# v1.net
KiCad netlist of a schematic drawn in EAGLE
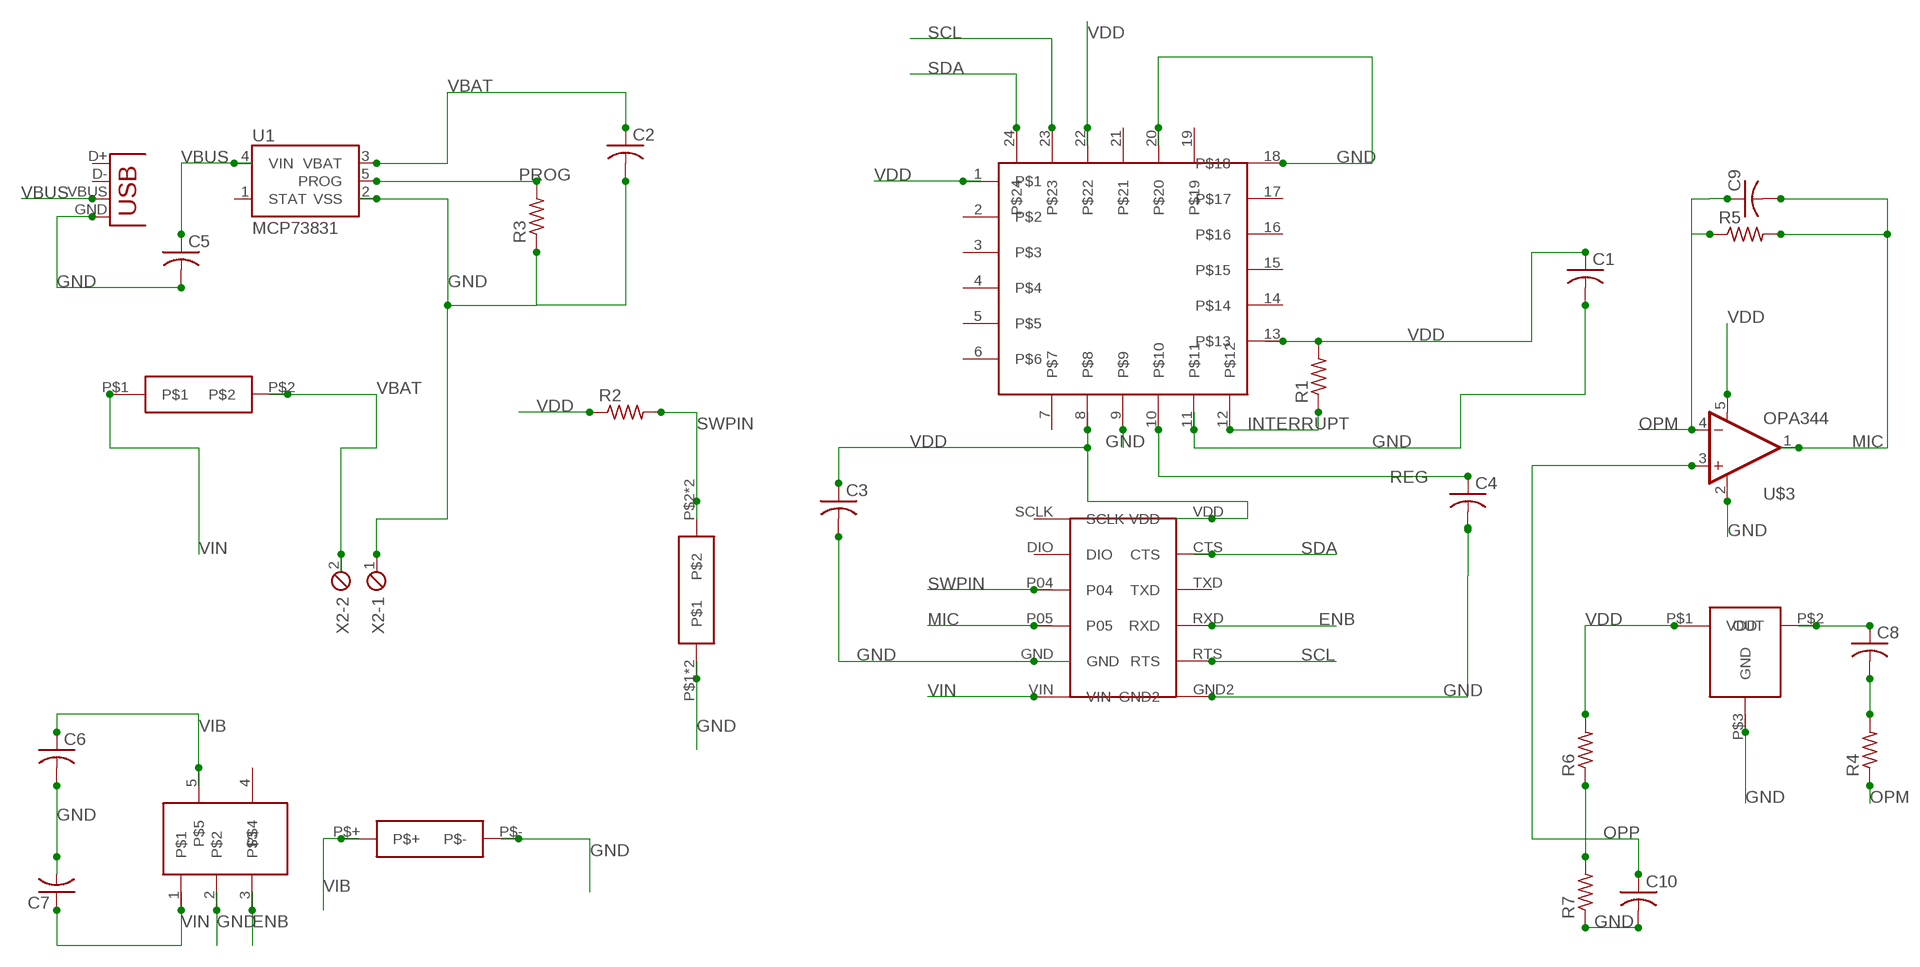
[diagram p0: schematic, sheet 1]

(export (version "E")
  (design (tool "Eeschema 10.0.6"))
  (components
    (comp (ref "C1")
      (value "C-USC0402K")
      (footprint "eagle-import:C0402K")
      (libsource (lib "eagle-import") (part "C-USC0402K"))
    )
    (comp (ref "C2")
      (value "C-USC0402K")
      (footprint "eagle-import:C0402K")
      (libsource (lib "eagle-import") (part "C-USC0402K"))
    )
    (comp (ref "C3")
      (value "C-USC0402K")
      (footprint "eagle-import:C0402K")
      (libsource (lib "eagle-import") (part "C-USC0402K"))
    )
    (comp (ref "C4")
      (value "C-USC0402K")
      (footprint "eagle-import:C0402K")
      (libsource (lib "eagle-import") (part "C-USC0402K"))
    )
    (comp (ref "C5")
      (value "C-USC0402K")
      (footprint "eagle-import:C0402K")
      (libsource (lib "eagle-import") (part "C-USC0402K"))
    )
    (comp (ref "C6")
      (value "C-USC0402K")
      (footprint "eagle-import:C0402K")
      (libsource (lib "eagle-import") (part "C-USC0402K"))
    )
    (comp (ref "C7")
      (value "C-USC0402K")
      (footprint "eagle-import:C0402K")
      (libsource (lib "eagle-import") (part "C-USC0402K"))
    )
    (comp (ref "C8")
      (value "C-USC0402K")
      (footprint "eagle-import:C0402K")
      (libsource (lib "eagle-import") (part "C-USC0402K"))
    )
    (comp (ref "C9")
      (value "C-USC0402K")
      (footprint "eagle-import:C0402K")
      (libsource (lib "eagle-import") (part "C-USC0402K"))
    )
    (comp (ref "C10")
      (value "C-USC0402K")
      (footprint "eagle-import:C0402K")
      (libsource (lib "eagle-import") (part "C-USC0402K"))
    )
    (comp (ref "R1")
      (value "R-US_R0402")
      (footprint "eagle-import:R0402")
      (libsource (lib "eagle-import") (part "R-US_R0402"))
    )
    (comp (ref "R2")
      (value "R-US_R0402")
      (footprint "eagle-import:R0402")
      (libsource (lib "eagle-import") (part "R-US_R0402"))
    )
    (comp (ref "R3")
      (value "R-US_R0402")
      (footprint "eagle-import:R0402")
      (libsource (lib "eagle-import") (part "R-US_R0402"))
    )
    (comp (ref "R4")
      (value "R-US_R0402")
      (footprint "eagle-import:R0402")
      (libsource (lib "eagle-import") (part "R-US_R0402"))
    )
    (comp (ref "R5")
      (value "R-US_R0402")
      (footprint "eagle-import:R0402")
      (libsource (lib "eagle-import") (part "R-US_R0402"))
    )
    (comp (ref "R6")
      (value "R-US_R0402")
      (footprint "eagle-import:R0402")
      (libsource (lib "eagle-import") (part "R-US_R0402"))
    )
    (comp (ref "R7")
      (value "R-US_R0402")
      (footprint "eagle-import:R0402")
      (libsource (lib "eagle-import") (part "R-US_R0402"))
    )
    (comp (ref "U$1")
      (value "NANOBLE")
      (footprint "eagle-import:NANOBLE")
      (libsource (lib "eagle-import") (part "NANOBLE"))
    )
    (comp (ref "U$2")
      (value "MICROPHONE")
      (footprint "eagle-import:MICROPHONE")
      (libsource (lib "eagle-import") (part "MICROPHONE"))
    )
    (comp (ref "U$3")
      (value "OPA344")
      (footprint "eagle-import:SOT23-5")
      (libsource (lib "eagle-import") (part "OPA344"))
    )
    (comp (ref "U$4")
      (value "LP5907")
      (footprint "eagle-import:SOT23-5")
      (libsource (lib "eagle-import") (part "LP5907"))
    )
    (comp (ref "U$5")
      (value "TACTILE")
      (footprint "eagle-import:TACTILE")
      (libsource (lib "eagle-import") (part "TACTILE"))
    )
    (comp (ref "U$6")
      (value "SWITCH")
      (footprint "eagle-import:SWITCH2")
      (libsource (lib "eagle-import") (part "SWITCH"))
    )
    (comp (ref "U$7")
      (value "VIBRATOR")
      (footprint "eagle-import:VIBRATOR")
      (libsource (lib "eagle-import") (part "VIBRATOR"))
    )
    (comp (ref "U$8")
      (value "COMPASSE")
      (footprint "eagle-import:QFN-24-USB")
      (libsource (lib "eagle-import") (part "COMPASSE"))
    )
    (comp (ref "U1")
      (value "MCP73831")
      (footprint "eagle-import:SOT23-5")
      (libsource (lib "eagle-import") (part "MCP73831"))
    )
    (comp (ref "X1")
      (value "USB-MICROB")
      (footprint "eagle-import:USB-MICROB")
      (libsource (lib "eagle-import") (part "USB-MICROB"))
    )
    (comp (ref "X2")
      (value "MPT2")
      (footprint "eagle-import:2POL254")
      (libsource (lib "eagle-import") (part "MPT2"))
    )
  )
  (nets
    (net (code "1") (name "/ENB") (class "Default")
      (node (ref "U$1") (pin "RXD") (pinfunction "RXD_RXD") (pintype "bidirectional"))
      (node (ref "U$4") (pin "3") (pinfunction "P$3_3") (pintype "bidirectional"))
    )
    (net (code "2") (name "/GND") (class "Default")
      (node (ref "C1") (pin "2") (pinfunction "2_2") (pintype "passive"))
      (node (ref "C10") (pin "2") (pinfunction "2_2") (pintype "passive"))
      (node (ref "C2") (pin "2") (pinfunction "2_2") (pintype "passive"))
      (node (ref "C3") (pin "2") (pinfunction "2_2") (pintype "passive"))
      (node (ref "C4") (pin "2") (pinfunction "2_2") (pintype "passive"))
      (node (ref "C5") (pin "2") (pinfunction "2_2") (pintype "passive"))
      (node (ref "C6") (pin "2") (pinfunction "2_2") (pintype "passive"))
      (node (ref "C7") (pin "2") (pinfunction "2_2") (pintype "passive"))
      (node (ref "R3") (pin "1") (pinfunction "1_1") (pintype "passive"))
      (node (ref "R7") (pin "1") (pinfunction "1_1") (pintype "passive"))
      (node (ref "U$1") (pin "GND") (pinfunction "GND_GND") (pintype "bidirectional"))
      (node (ref "U$1") (pin "GND2") (pinfunction "GND2_GND2") (pintype "bidirectional"))
      (node (ref "U$2") (pin "P$3") (pinfunction "GND_P$3") (pintype "bidirectional"))
      (node (ref "U$3") (pin "2") (pinfunction "V-_2") (pintype "power_in"))
      (node (ref "U$4") (pin "2") (pinfunction "P$2_2") (pintype "bidirectional"))
      (node (ref "U$5") (pin "P$1") (pinfunction "P$1_P$1") (pintype "bidirectional"))
      (node (ref "U$5") (pin "P$3") (pinfunction "P$1_P$3") (pintype "bidirectional"))
      (node (ref "U$7") (pin "P$-") (pinfunction "P$-_P$-") (pintype "bidirectional"))
      (node (ref "U$8") (pin "11") (pinfunction "P$11_11") (pintype "bidirectional"))
      (node (ref "U$8") (pin "18") (pinfunction "P$18_18") (pintype "bidirectional"))
      (node (ref "U$8") (pin "20") (pinfunction "P$20_20") (pintype "bidirectional"))
      (node (ref "U$8") (pin "9") (pinfunction "P$9_9") (pintype "bidirectional"))
      (node (ref "U1") (pin "2") (pinfunction "VSS_2") (pintype "power_in"))
      (node (ref "X1") (pin "GND") (pinfunction "GND_GND") (pintype "bidirectional"))
      (node (ref "X2") (pin "1") (pinfunction "1_1") (pintype "passive"))
    )
    (net (code "3") (name "/INTERRUPT") (class "Default")
      (node (ref "R1") (pin "1") (pinfunction "1_1") (pintype "passive"))
      (node (ref "U$8") (pin "12") (pinfunction "P$12_12") (pintype "bidirectional"))
    )
    (net (code "4") (name "/MIC") (class "Default")
      (node (ref "C9") (pin "2") (pinfunction "2_2") (pintype "passive"))
      (node (ref "R5") (pin "2") (pinfunction "2_2") (pintype "passive"))
      (node (ref "U$1") (pin "P05") (pinfunction "P05_P05") (pintype "bidirectional"))
      (node (ref "U$3") (pin "1") (pinfunction "OUT_1") (pintype "output"))
    )
    (net (code "5") (name "/OPM") (class "Default")
      (node (ref "C9") (pin "1") (pinfunction "1_1") (pintype "passive"))
      (node (ref "R4") (pin "1") (pinfunction "1_1") (pintype "passive"))
      (node (ref "R5") (pin "1") (pinfunction "1_1") (pintype "passive"))
      (node (ref "U$3") (pin "4") (pinfunction "-IN_4") (pintype "input"))
    )
    (net (code "6") (name "/OPP") (class "Default")
      (node (ref "C10") (pin "1") (pinfunction "1_1") (pintype "passive"))
      (node (ref "R6") (pin "1") (pinfunction "1_1") (pintype "passive"))
      (node (ref "R7") (pin "2") (pinfunction "2_2") (pintype "passive"))
      (node (ref "U$3") (pin "3") (pinfunction "+IN_3") (pintype "input"))
    )
    (net (code "7") (name "/PROG") (class "Default")
      (node (ref "R3") (pin "2") (pinfunction "2_2") (pintype "passive"))
      (node (ref "U1") (pin "5") (pinfunction "PROG_5") (pintype "input"))
    )
    (net (code "8") (name "/REG") (class "Default")
      (node (ref "C4") (pin "1") (pinfunction "1_1") (pintype "passive"))
      (node (ref "U$8") (pin "10") (pinfunction "P$10_10") (pintype "bidirectional"))
    )
    (net (code "9") (name "/SCL") (class "Default")
      (node (ref "U$1") (pin "RTS") (pinfunction "RTS_RTS") (pintype "bidirectional"))
      (node (ref "U$8") (pin "23") (pinfunction "P$23_23") (pintype "bidirectional"))
    )
    (net (code "10") (name "/SDA") (class "Default")
      (node (ref "U$1") (pin "CTS") (pinfunction "CTS_CTS") (pintype "bidirectional"))
      (node (ref "U$8") (pin "24") (pinfunction "P$24_24") (pintype "bidirectional"))
    )
    (net (code "11") (name "/SWPIN") (class "Default")
      (node (ref "R2") (pin "2") (pinfunction "2_2") (pintype "passive"))
      (node (ref "U$1") (pin "P04") (pinfunction "P04_P04") (pintype "bidirectional"))
      (node (ref "U$5") (pin "P$2") (pinfunction "P$2_P$2") (pintype "bidirectional"))
      (node (ref "U$5") (pin "P$4") (pinfunction "P$2_P$4") (pintype "bidirectional"))
    )
    (net (code "12") (name "/VBAT") (class "Default")
      (node (ref "C2") (pin "1") (pinfunction "1_1") (pintype "passive"))
      (node (ref "U$6") (pin "P$2") (pinfunction "P$2_P$2") (pintype "bidirectional"))
      (node (ref "U1") (pin "3") (pinfunction "VBAT_3") (pintype "power_in"))
      (node (ref "X2") (pin "2") (pinfunction "1_2") (pintype "passive"))
    )
    (net (code "13") (name "/VBUS") (class "Default")
      (node (ref "C5") (pin "1") (pinfunction "1_1") (pintype "passive"))
      (node (ref "U1") (pin "4") (pinfunction "VIN_4") (pintype "power_in"))
      (node (ref "X1") (pin "VBUS") (pinfunction "VBUS_VBUS") (pintype "bidirectional"))
    )
    (net (code "14") (name "/VDD") (class "Default")
      (node (ref "C1") (pin "1") (pinfunction "1_1") (pintype "passive"))
      (node (ref "C3") (pin "1") (pinfunction "1_1") (pintype "passive"))
      (node (ref "R1") (pin "2") (pinfunction "2_2") (pintype "passive"))
      (node (ref "R2") (pin "1") (pinfunction "1_1") (pintype "passive"))
      (node (ref "R6") (pin "2") (pinfunction "2_2") (pintype "passive"))
      (node (ref "U$1") (pin "VDD") (pinfunction "VDD_VDD") (pintype "bidirectional"))
      (node (ref "U$2") (pin "P$1") (pinfunction "VDD_P$1") (pintype "bidirectional"))
      (node (ref "U$3") (pin "5") (pinfunction "V+_5") (pintype "power_in"))
      (node (ref "U$8") (pin "1") (pinfunction "P$1_1") (pintype "bidirectional"))
      (node (ref "U$8") (pin "13") (pinfunction "P$13_13") (pintype "bidirectional"))
      (node (ref "U$8") (pin "22") (pinfunction "P$22_22") (pintype "bidirectional"))
      (node (ref "U$8") (pin "8") (pinfunction "P$8_8") (pintype "bidirectional"))
    )
    (net (code "15") (name "/VIB") (class "Default")
      (node (ref "C6") (pin "1") (pinfunction "1_1") (pintype "passive"))
      (node (ref "U$4") (pin "5") (pinfunction "P$5_5") (pintype "bidirectional"))
      (node (ref "U$7") (pin "P$+") (pinfunction "P$+_P$+") (pintype "bidirectional"))
    )
    (net (code "16") (name "/VIN") (class "Default")
      (node (ref "C7") (pin "1") (pinfunction "1_1") (pintype "passive"))
      (node (ref "U$1") (pin "VIN") (pinfunction "VIN_VIN") (pintype "bidirectional"))
      (node (ref "U$4") (pin "1") (pinfunction "P$1_1") (pintype "bidirectional"))
      (node (ref "U$6") (pin "P$1") (pinfunction "P$1_P$1") (pintype "bidirectional"))
    )
    (net (code "17") (name "Net-(C8-Pad2)") (class "Default")
      (node (ref "C8") (pin "2") (pinfunction "2_2") (pintype "passive"))
      (node (ref "R4") (pin "2") (pinfunction "2_2") (pintype "passive"))
    )
    (net (code "18") (name "Net-(U$2-OUT)") (class "Default")
      (node (ref "C8") (pin "1") (pinfunction "1_1") (pintype "passive"))
      (node (ref "U$2") (pin "P$2") (pinfunction "OUT_P$2") (pintype "bidirectional"))
    )
    (net (code "19") (name "unconnected-(U$1-PadDIO)") (class "Default")
      (node (ref "U$1") (pin "DIO") (pinfunction "DIO_DIO") (pintype "bidirectional"))
    )
    (net (code "20") (name "unconnected-(U$1-PadSCLK)") (class "Default")
      (node (ref "U$1") (pin "SCLK") (pinfunction "SCLK_SCLK") (pintype "bidirectional"))
    )
    (net (code "21") (name "unconnected-(U$1-PadTXD)") (class "Default")
      (node (ref "U$1") (pin "TXD") (pinfunction "TXD_TXD") (pintype "bidirectional"))
    )
    (net (code "22") (name "unconnected-(U$4-P$4-Pad4)") (class "Default")
      (node (ref "U$4") (pin "4") (pinfunction "P$4_4") (pintype "bidirectional"))
    )
    (net (code "23") (name "unconnected-(U$8-P$2-Pad2)") (class "Default")
      (node (ref "U$8") (pin "2") (pinfunction "P$2_2") (pintype "bidirectional"))
    )
    (net (code "24") (name "unconnected-(U$8-P$3-Pad3)") (class "Default")
      (node (ref "U$8") (pin "3") (pinfunction "P$3_3") (pintype "bidirectional"))
    )
    (net (code "25") (name "unconnected-(U$8-P$4-Pad4)") (class "Default")
      (node (ref "U$8") (pin "4") (pinfunction "P$4_4") (pintype "bidirectional"))
    )
    (net (code "26") (name "unconnected-(U$8-P$5-Pad5)") (class "Default")
      (node (ref "U$8") (pin "5") (pinfunction "P$5_5") (pintype "bidirectional"))
    )
    (net (code "27") (name "unconnected-(U$8-P$6-Pad6)") (class "Default")
      (node (ref "U$8") (pin "6") (pinfunction "P$6_6") (pintype "bidirectional"))
    )
    (net (code "28") (name "unconnected-(U$8-P$7-Pad7)") (class "Default")
      (node (ref "U$8") (pin "7") (pinfunction "P$7_7") (pintype "bidirectional"))
    )
    (net (code "29") (name "unconnected-(U$8-P$14-Pad14)") (class "Default")
      (node (ref "U$8") (pin "14") (pinfunction "P$14_14") (pintype "bidirectional"))
    )
    (net (code "30") (name "unconnected-(U$8-P$15-Pad15)") (class "Default")
      (node (ref "U$8") (pin "15") (pinfunction "P$15_15") (pintype "bidirectional"))
    )
    (net (code "31") (name "unconnected-(U$8-P$16-Pad16)") (class "Default")
      (node (ref "U$8") (pin "16") (pinfunction "P$16_16") (pintype "bidirectional"))
    )
    (net (code "32") (name "unconnected-(U$8-P$17-Pad17)") (class "Default")
      (node (ref "U$8") (pin "17") (pinfunction "P$17_17") (pintype "bidirectional"))
    )
    (net (code "33") (name "unconnected-(U$8-P$19-Pad19)") (class "Default")
      (node (ref "U$8") (pin "19") (pinfunction "P$19_19") (pintype "bidirectional"))
    )
    (net (code "34") (name "unconnected-(U$8-P$21-Pad21)") (class "Default")
      (node (ref "U$8") (pin "21") (pinfunction "P$21_21") (pintype "bidirectional"))
    )
    (net (code "35") (name "unconnected-(U1-STAT-Pad1)") (class "Default")
      (node (ref "U1") (pin "1") (pinfunction "STAT_1") (pintype "output"))
    )
    (net (code "36") (name "unconnected-(X1-PadD+)") (class "Default")
      (node (ref "X1") (pin "D+") (pinfunction "D+_D+") (pintype "bidirectional"))
    )
    (net (code "37") (name "unconnected-(X1-PadD-)") (class "Default")
      (node (ref "X1") (pin "D-") (pinfunction "D-_D-") (pintype "bidirectional"))
    )
  )
)
